# PCB-3_5MM_Input_Adapter.net
KiCad netlist of a schematic drawn in EAGLE
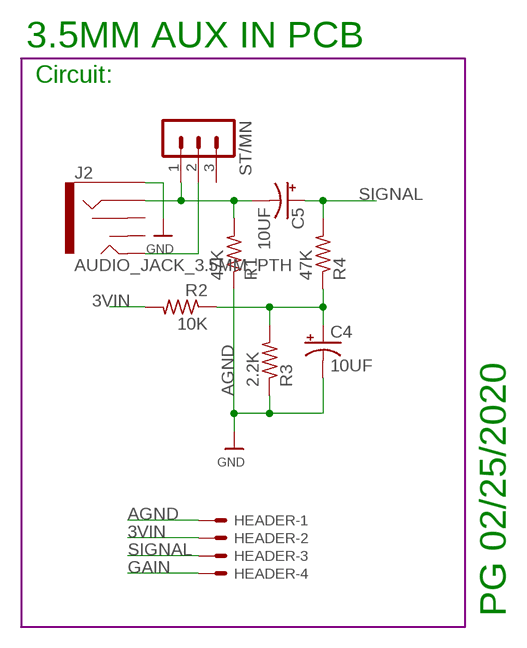
[diagram p0: schematic, sheet 1]

(export (version "E")
  (design (tool "Eeschema 10.0.6"))
  (components
    (comp (ref "C4")
      (value "10UF")
      (footprint "eagle-import:E5-8,5")
      (libsource (lib "eagle-import") (part "CPOL-USE5-8.5"))
    )
    (comp (ref "C5")
      (value "10UF")
      (footprint "eagle-import:E5-8,5")
      (libsource (lib "eagle-import") (part "CPOL-USE5-8.5"))
    )
    (comp (ref "HEADER")
      (value "KK-156-4")
      (footprint "eagle-import:KK-156-4")
      (fields (field (name "MF") "MOLEX"))
      (libsource (lib "eagle-import") (part "KK-156-4"))
    )
    (comp (ref "J2")
      (value "AUDIO_JACK_3.5MM_PTH")
      (footprint "eagle-import:AUDIO-JACK")
      (libsource (lib "eagle-import") (part "AUDIO_JACK_3.5MM_PTH"))
    )
    (comp (ref "R1")
      (value "47K")
      (footprint "eagle-import:R1206")
      (libsource (lib "eagle-import") (part "R-US_R1206"))
    )
    (comp (ref "R2")
      (value "10K")
      (footprint "eagle-import:R1206")
      (libsource (lib "eagle-import") (part "R-US_R1206"))
    )
    (comp (ref "R3")
      (value "2.2K")
      (footprint "eagle-import:R1206")
      (libsource (lib "eagle-import") (part "R-US_R1206"))
    )
    (comp (ref "R4")
      (value "47K")
      (footprint "eagle-import:R1206")
      (libsource (lib "eagle-import") (part "R-US_R1206"))
    )
    (comp (ref "ST/MN")
      (value "MA03-1")
      (footprint "eagle-import:MA03-1")
      (libsource (lib "eagle-import") (part "MA03-1"))
    )
  )
  (nets
    (net (code "1") (name "/3VIN") (class "Default")
      (node (ref "HEADER") (pin "2") (pinfunction "S_2") (pintype "passive"))
      (node (ref "R2") (pin "2") (pinfunction "2_2") (pintype "passive"))
    )
    (net (code "2") (name "/GAIN") (class "Default")
      (node (ref "HEADER") (pin "4") (pinfunction "S_4") (pintype "passive"))
    )
    (net (code "3") (name "/SIGNAL") (class "Default")
      (node (ref "C5") (pin "+") (pinfunction "+_+") (pintype "passive"))
      (node (ref "HEADER") (pin "3") (pinfunction "S_3") (pintype "passive"))
      (node (ref "R4") (pin "2") (pinfunction "2_2") (pintype "passive"))
    )
    (net (code "4") (name "GND") (class "Default")
      (node (ref "C4") (pin "-") (pinfunction "-_-") (pintype "passive"))
      (node (ref "HEADER") (pin "1") (pinfunction "S_1") (pintype "passive"))
      (node (ref "J2") (pin "SLEEVE") (pinfunction "SLEEVE_SLEEVE") (pintype "bidirectional"))
      (node (ref "R1") (pin "1") (pinfunction "1_1") (pintype "passive"))
      (node (ref "R3") (pin "1") (pinfunction "1_1") (pintype "passive"))
    )
    (net (code "5") (name "Net-(C4-Pad+)") (class "Default")
      (node (ref "C4") (pin "+") (pinfunction "+_+") (pintype "passive"))
      (node (ref "R2") (pin "1") (pinfunction "1_1") (pintype "passive"))
      (node (ref "R3") (pin "2") (pinfunction "2_2") (pintype "passive"))
      (node (ref "R4") (pin "1") (pinfunction "1_1") (pintype "passive"))
    )
    (net (code "6") (name "Net-(C5-Pad-)") (class "Default")
      (node (ref "C5") (pin "-") (pinfunction "-_-") (pintype "passive"))
      (node (ref "J2") (pin "RING") (pinfunction "RING_RING") (pintype "bidirectional"))
      (node (ref "R1") (pin "2") (pinfunction "2_2") (pintype "passive"))
      (node (ref "ST/MN") (pin "1") (pinfunction "1_1") (pintype "passive"))
    )
    (net (code "7") (name "Net-(J2-PadTIP)") (class "Default")
      (node (ref "J2") (pin "TIP") (pinfunction "TIP_TIP") (pintype "bidirectional"))
      (node (ref "ST/MN") (pin "2") (pinfunction "2_2") (pintype "passive"))
    )
    (net (code "8") (name "unconnected-(J2-PadRSH)") (class "Default")
      (node (ref "J2") (pin "RSH") (pinfunction "RSH_RSH") (pintype "bidirectional"))
    )
    (net (code "9") (name "unconnected-(J2-PadTSH)") (class "Default")
      (node (ref "J2") (pin "TSH") (pinfunction "TSH_TSH") (pintype "bidirectional"))
    )
    (net (code "10") (name "unconnected-(ST/MN-Pad3)") (class "Default")
      (node (ref "ST/MN") (pin "3") (pinfunction "3_3") (pintype "passive"))
    )
  )
)
